# FPGA_MONITOR.net
KiCad netlist of a schematic drawn in Altium Designer
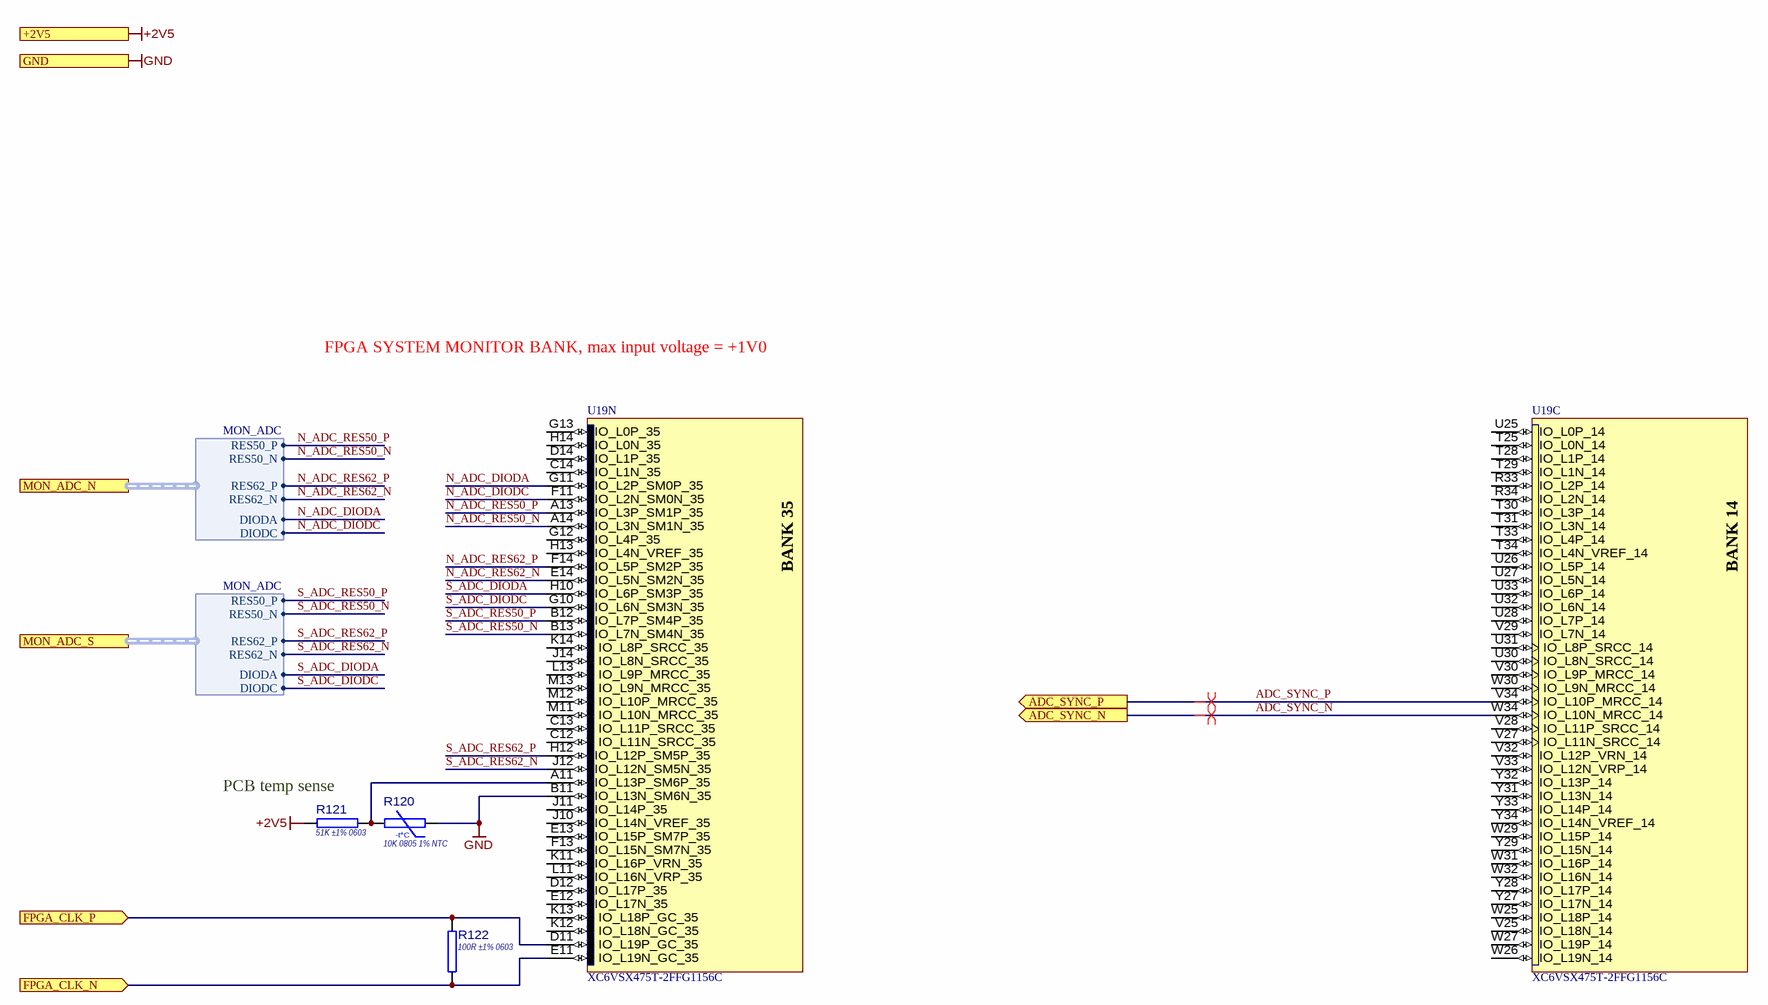
[diagram p0: FPGA_MONITOR.SchDoc]

(export (version "E")
  (design (tool "Eeschema 10.0.6"))
  (components
    (comp (ref "R120")
      (value "10K 0805 1% NTC")
      (footprint "RESC2012N")
      (description "10K NTC resistor 1%  0805 (2012 metric)")
      (fields (field (name "PARTNUMBER") "NTCS0805E3103FLT"))
      (libsource (lib "Omnisys Vault") (part "RES-2PIN-NTC"))
    )
    (comp (ref "R121")
      (value "51K ±1% 0603")
      (footprint "RESC1608N")
      (description "51K ±1% ±100 ppm/˚C 0.10W 75V 0603 (1608 metric)")
      (fields (field (name "POWER") "100mW") (field (name "TOLERANCE") "1%"))
      (libsource (lib "Omnisys Vault") (part "RES-2PIN"))
    )
    (comp (ref "R122")
      (value "100R ±1% 0603")
      (footprint "RESC1608N")
      (description "100R ±1% ±100 ppm/˚C 0.10W 75V 0603 (1608 metric)")
      (fields (field (name "POWER") "100mW") (field (name "TOLERANCE") "1%"))
      (libsource (lib "Omnisys Vault") (part "RES-2PIN"))
    )
    (comp (ref "U19")
      (value "XC6VSX475T-2FFG1156C")
      (footprint "FFG1156")
      (libsource (lib "Altium Content Vault") (part "FPGA-XVR6-XC6VXXXXXT-GA1156"))
    )
  )
  (nets
    (net (code "2") (name "+2V5") (class "Default")
      (node (ref "R121") (pin "1") (pinfunction "1_1") (pintype "passive"))
    )
    (net (code "3") (name "/ADC_SYNC_N") (class "Default")
      (node (ref "U19") (pin "W34") (pinfunction "IO_L10N_MRCC_14_W34") (pintype "bidirectional"))
    )
    (net (code "4") (name "/ADC_SYNC_P") (class "Default")
      (node (ref "U19") (pin "V34") (pinfunction "IO_L10P_MRCC_14_V34") (pintype "bidirectional"))
    )
    (net (code "5") (name "/FPGA_CLK_N") (class "Default")
      (node (ref "R122") (pin "1") (pinfunction "1_1") (pintype "passive"))
      (node (ref "U19") (pin "E11") (pinfunction "IO_L19N_GC_35_E11") (pintype "bidirectional"))
    )
    (net (code "6") (name "/FPGA_CLK_P") (class "Default")
      (node (ref "R122") (pin "2") (pinfunction "2_2") (pintype "passive"))
      (node (ref "U19") (pin "D11") (pinfunction "IO_L19P_GC_35_D11") (pintype "bidirectional"))
    )
    (net (code "7") (name "/N_ADC_DIODA") (class "Default")
      (node (ref "U19") (pin "G11") (pinfunction "IO_L2P_SM0P_35_G11") (pintype "bidirectional"))
    )
    (net (code "8") (name "/N_ADC_DIODC") (class "Default")
      (node (ref "U19") (pin "F11") (pinfunction "IO_L2N_SM0N_35_F11") (pintype "bidirectional"))
    )
    (net (code "9") (name "/N_ADC_RES50_N") (class "Default")
      (node (ref "U19") (pin "A14") (pinfunction "IO_L3N_SM1N_35_A14") (pintype "bidirectional"))
    )
    (net (code "10") (name "/N_ADC_RES50_P") (class "Default")
      (node (ref "U19") (pin "A13") (pinfunction "IO_L3P_SM1P_35_A13") (pintype "bidirectional"))
    )
    (net (code "11") (name "/N_ADC_RES62_N") (class "Default")
      (node (ref "U19") (pin "E14") (pinfunction "IO_L5N_SM2N_35_E14") (pintype "bidirectional"))
    )
    (net (code "12") (name "/N_ADC_RES62_P") (class "Default")
      (node (ref "U19") (pin "F14") (pinfunction "IO_L5P_SM2P_35_F14") (pintype "bidirectional"))
    )
    (net (code "13") (name "/S_ADC_DIODA") (class "Default")
      (node (ref "U19") (pin "H10") (pinfunction "IO_L6P_SM3P_35_H10") (pintype "bidirectional"))
    )
    (net (code "14") (name "/S_ADC_DIODC") (class "Default")
      (node (ref "U19") (pin "G10") (pinfunction "IO_L6N_SM3N_35_G10") (pintype "bidirectional"))
    )
    (net (code "15") (name "/S_ADC_RES50_N") (class "Default")
      (node (ref "U19") (pin "B13") (pinfunction "IO_L7N_SM4N_35_B13") (pintype "bidirectional"))
    )
    (net (code "16") (name "/S_ADC_RES50_P") (class "Default")
      (node (ref "U19") (pin "B12") (pinfunction "IO_L7P_SM4P_35_B12") (pintype "bidirectional"))
    )
    (net (code "17") (name "/S_ADC_RES62_N") (class "Default")
      (node (ref "U19") (pin "J12") (pinfunction "IO_L12N_SM5N_35_J12") (pintype "bidirectional"))
    )
    (net (code "18") (name "/S_ADC_RES62_P") (class "Default")
      (node (ref "U19") (pin "H12") (pinfunction "IO_L12P_SM5P_35_H12") (pintype "bidirectional"))
    )
    (net (code "20") (name "GND") (class "Default")
      (node (ref "R120") (pin "1") (pinfunction "1_1") (pintype "passive"))
      (node (ref "U19") (pin "B11") (pinfunction "IO_L13N_SM6N_35_B11") (pintype "bidirectional"))
    )
    (net (code "21") (name "Net-(U19N-IO_L13P_SM6P_35)") (class "Default")
      (node (ref "R120") (pin "2") (pinfunction "2_2") (pintype "passive"))
      (node (ref "R121") (pin "2") (pinfunction "2_2") (pintype "passive"))
      (node (ref "U19") (pin "A11") (pinfunction "IO_L13P_SM6P_35_A11") (pintype "bidirectional"))
    )
    (net (code "22") (name "unconnected-(U19C-IO_L0N_14-PadT25)") (class "Default")
      (node (ref "U19") (pin "T25") (pinfunction "IO_L0N_14_T25") (pintype "bidirectional"))
    )
    (net (code "23") (name "unconnected-(U19C-IO_L0P_14-PadU25)") (class "Default")
      (node (ref "U19") (pin "U25") (pinfunction "IO_L0P_14_U25") (pintype "bidirectional"))
    )
    (net (code "24") (name "unconnected-(U19C-IO_L1N_14-PadT29)") (class "Default")
      (node (ref "U19") (pin "T29") (pinfunction "IO_L1N_14_T29") (pintype "bidirectional"))
    )
    (net (code "25") (name "unconnected-(U19C-IO_L1P_14-PadT28)") (class "Default")
      (node (ref "U19") (pin "T28") (pinfunction "IO_L1P_14_T28") (pintype "bidirectional"))
    )
    (net (code "26") (name "unconnected-(U19C-IO_L2N_14-PadR34)") (class "Default")
      (node (ref "U19") (pin "R34") (pinfunction "IO_L2N_14_R34") (pintype "bidirectional"))
    )
    (net (code "27") (name "unconnected-(U19C-IO_L2P_14-PadR33)") (class "Default")
      (node (ref "U19") (pin "R33") (pinfunction "IO_L2P_14_R33") (pintype "bidirectional"))
    )
    (net (code "28") (name "unconnected-(U19C-IO_L3N_14-PadT31)") (class "Default")
      (node (ref "U19") (pin "T31") (pinfunction "IO_L3N_14_T31") (pintype "bidirectional"))
    )
    (net (code "29") (name "unconnected-(U19C-IO_L3P_14-PadT30)") (class "Default")
      (node (ref "U19") (pin "T30") (pinfunction "IO_L3P_14_T30") (pintype "bidirectional"))
    )
    (net (code "30") (name "unconnected-(U19C-IO_L4N_VREF_14-PadT34)") (class "Default")
      (node (ref "U19") (pin "T34") (pinfunction "IO_L4N_VREF_14_T34") (pintype "bidirectional"))
    )
    (net (code "31") (name "unconnected-(U19C-IO_L4P_14-PadT33)") (class "Default")
      (node (ref "U19") (pin "T33") (pinfunction "IO_L4P_14_T33") (pintype "bidirectional"))
    )
    (net (code "32") (name "unconnected-(U19C-IO_L5N_14-PadU27)") (class "Default")
      (node (ref "U19") (pin "U27") (pinfunction "IO_L5N_14_U27") (pintype "bidirectional"))
    )
    (net (code "33") (name "unconnected-(U19C-IO_L5P_14-PadU26)") (class "Default")
      (node (ref "U19") (pin "U26") (pinfunction "IO_L5P_14_U26") (pintype "bidirectional"))
    )
    (net (code "34") (name "unconnected-(U19C-IO_L6N_14-PadU32)") (class "Default")
      (node (ref "U19") (pin "U32") (pinfunction "IO_L6N_14_U32") (pintype "bidirectional"))
    )
    (net (code "35") (name "unconnected-(U19C-IO_L6P_14-PadU33)") (class "Default")
      (node (ref "U19") (pin "U33") (pinfunction "IO_L6P_14_U33") (pintype "bidirectional"))
    )
    (net (code "36") (name "unconnected-(U19C-IO_L7N_14-PadV29)") (class "Default")
      (node (ref "U19") (pin "V29") (pinfunction "IO_L7N_14_V29") (pintype "bidirectional"))
    )
    (net (code "37") (name "unconnected-(U19C-IO_L7P_14-PadU28)") (class "Default")
      (node (ref "U19") (pin "U28") (pinfunction "IO_L7P_14_U28") (pintype "bidirectional"))
    )
    (net (code "38") (name "unconnected-(U19C-IO_L8N_SRCC_14-PadU30)") (class "Default")
      (node (ref "U19") (pin "U30") (pinfunction "IO_L8N_SRCC_14_U30") (pintype "bidirectional"))
    )
    (net (code "39") (name "unconnected-(U19C-IO_L8P_SRCC_14-PadU31)") (class "Default")
      (node (ref "U19") (pin "U31") (pinfunction "IO_L8P_SRCC_14_U31") (pintype "bidirectional"))
    )
    (net (code "40") (name "unconnected-(U19C-IO_L9N_MRCC_14-PadW30)") (class "Default")
      (node (ref "U19") (pin "W30") (pinfunction "IO_L9N_MRCC_14_W30") (pintype "bidirectional"))
    )
    (net (code "41") (name "unconnected-(U19C-IO_L9P_MRCC_14-PadV30)") (class "Default")
      (node (ref "U19") (pin "V30") (pinfunction "IO_L9P_MRCC_14_V30") (pintype "bidirectional"))
    )
    (net (code "42") (name "unconnected-(U19C-IO_L11N_SRCC_14-PadV27)") (class "Default")
      (node (ref "U19") (pin "V27") (pinfunction "IO_L11N_SRCC_14_V27") (pintype "bidirectional"))
    )
    (net (code "43") (name "unconnected-(U19C-IO_L11P_SRCC_14-PadV28)") (class "Default")
      (node (ref "U19") (pin "V28") (pinfunction "IO_L11P_SRCC_14_V28") (pintype "bidirectional"))
    )
    (net (code "44") (name "unconnected-(U19C-IO_L12N_VRP_14-PadV33)") (class "Default")
      (node (ref "U19") (pin "V33") (pinfunction "IO_L12N_VRP_14_V33") (pintype "bidirectional"))
    )
    (net (code "45") (name "unconnected-(U19C-IO_L12P_VRN_14-PadV32)") (class "Default")
      (node (ref "U19") (pin "V32") (pinfunction "IO_L12P_VRN_14_V32") (pintype "bidirectional"))
    )
    (net (code "46") (name "unconnected-(U19C-IO_L13N_14-PadY31)") (class "Default")
      (node (ref "U19") (pin "Y31") (pinfunction "IO_L13N_14_Y31") (pintype "bidirectional"))
    )
    (net (code "47") (name "unconnected-(U19C-IO_L13P_14-PadY32)") (class "Default")
      (node (ref "U19") (pin "Y32") (pinfunction "IO_L13P_14_Y32") (pintype "bidirectional"))
    )
    (net (code "48") (name "unconnected-(U19C-IO_L14N_VREF_14-PadY34)") (class "Default")
      (node (ref "U19") (pin "Y34") (pinfunction "IO_L14N_VREF_14_Y34") (pintype "bidirectional"))
    )
    (net (code "49") (name "unconnected-(U19C-IO_L14P_14-PadY33)") (class "Default")
      (node (ref "U19") (pin "Y33") (pinfunction "IO_L14P_14_Y33") (pintype "bidirectional"))
    )
    (net (code "50") (name "unconnected-(U19C-IO_L15N_14-PadY29)") (class "Default")
      (node (ref "U19") (pin "Y29") (pinfunction "IO_L15N_14_Y29") (pintype "bidirectional"))
    )
    (net (code "51") (name "unconnected-(U19C-IO_L15P_14-PadW29)") (class "Default")
      (node (ref "U19") (pin "W29") (pinfunction "IO_L15P_14_W29") (pintype "bidirectional"))
    )
    (net (code "52") (name "unconnected-(U19C-IO_L16N_14-PadW32)") (class "Default")
      (node (ref "U19") (pin "W32") (pinfunction "IO_L16N_14_W32") (pintype "bidirectional"))
    )
    (net (code "53") (name "unconnected-(U19C-IO_L16P_14-PadW31)") (class "Default")
      (node (ref "U19") (pin "W31") (pinfunction "IO_L16P_14_W31") (pintype "bidirectional"))
    )
    (net (code "54") (name "unconnected-(U19C-IO_L17N_14-PadY27)") (class "Default")
      (node (ref "U19") (pin "Y27") (pinfunction "IO_L17N_14_Y27") (pintype "bidirectional"))
    )
    (net (code "55") (name "unconnected-(U19C-IO_L17P_14-PadY28)") (class "Default")
      (node (ref "U19") (pin "Y28") (pinfunction "IO_L17P_14_Y28") (pintype "bidirectional"))
    )
    (net (code "56") (name "unconnected-(U19C-IO_L18N_14-PadV25)") (class "Default")
      (node (ref "U19") (pin "V25") (pinfunction "IO_L18N_14_V25") (pintype "bidirectional"))
    )
    (net (code "57") (name "unconnected-(U19C-IO_L18P_14-PadW25)") (class "Default")
      (node (ref "U19") (pin "W25") (pinfunction "IO_L18P_14_W25") (pintype "bidirectional"))
    )
    (net (code "58") (name "unconnected-(U19C-IO_L19N_14-PadW26)") (class "Default")
      (node (ref "U19") (pin "W26") (pinfunction "IO_L19N_14_W26") (pintype "bidirectional"))
    )
    (net (code "59") (name "unconnected-(U19C-IO_L19P_14-PadW27)") (class "Default")
      (node (ref "U19") (pin "W27") (pinfunction "IO_L19P_14_W27") (pintype "bidirectional"))
    )
    (net (code "60") (name "unconnected-(U19N-IO_L0N_35-PadH14)") (class "Default")
      (node (ref "U19") (pin "H14") (pinfunction "IO_L0N_35_H14") (pintype "bidirectional"))
    )
    (net (code "61") (name "unconnected-(U19N-IO_L0P_35-PadG13)") (class "Default")
      (node (ref "U19") (pin "G13") (pinfunction "IO_L0P_35_G13") (pintype "bidirectional"))
    )
    (net (code "62") (name "unconnected-(U19N-IO_L1N_35-PadC14)") (class "Default")
      (node (ref "U19") (pin "C14") (pinfunction "IO_L1N_35_C14") (pintype "bidirectional"))
    )
    (net (code "63") (name "unconnected-(U19N-IO_L1P_35-PadD14)") (class "Default")
      (node (ref "U19") (pin "D14") (pinfunction "IO_L1P_35_D14") (pintype "bidirectional"))
    )
    (net (code "64") (name "unconnected-(U19N-IO_L4N_VREF_35-PadH13)") (class "Default")
      (node (ref "U19") (pin "H13") (pinfunction "IO_L4N_VREF_35_H13") (pintype "bidirectional"))
    )
    (net (code "65") (name "unconnected-(U19N-IO_L4P_35-PadG12)") (class "Default")
      (node (ref "U19") (pin "G12") (pinfunction "IO_L4P_35_G12") (pintype "bidirectional"))
    )
    (net (code "66") (name "unconnected-(U19N-IO_L8N_SRCC_35-PadJ14)") (class "Default")
      (node (ref "U19") (pin "J14") (pinfunction "IO_L8N_SRCC_35_J14") (pintype "bidirectional"))
    )
    (net (code "67") (name "unconnected-(U19N-IO_L8P_SRCC_35-PadK14)") (class "Default")
      (node (ref "U19") (pin "K14") (pinfunction "IO_L8P_SRCC_35_K14") (pintype "bidirectional"))
    )
    (net (code "68") (name "unconnected-(U19N-IO_L9N_MRCC_35-PadM13)") (class "Default")
      (node (ref "U19") (pin "M13") (pinfunction "IO_L9N_MRCC_35_M13") (pintype "bidirectional"))
    )
    (net (code "69") (name "unconnected-(U19N-IO_L9P_MRCC_35-PadL13)") (class "Default")
      (node (ref "U19") (pin "L13") (pinfunction "IO_L9P_MRCC_35_L13") (pintype "bidirectional"))
    )
    (net (code "70") (name "unconnected-(U19N-IO_L10N_MRCC_35-PadM11)") (class "Default")
      (node (ref "U19") (pin "M11") (pinfunction "IO_L10N_MRCC_35_M11") (pintype "bidirectional"))
    )
    (net (code "71") (name "unconnected-(U19N-IO_L10P_MRCC_35-PadM12)") (class "Default")
      (node (ref "U19") (pin "M12") (pinfunction "IO_L10P_MRCC_35_M12") (pintype "bidirectional"))
    )
    (net (code "72") (name "unconnected-(U19N-IO_L11N_SRCC_35-PadC12)") (class "Default")
      (node (ref "U19") (pin "C12") (pinfunction "IO_L11N_SRCC_35_C12") (pintype "bidirectional"))
    )
    (net (code "73") (name "unconnected-(U19N-IO_L11P_SRCC_35-PadC13)") (class "Default")
      (node (ref "U19") (pin "C13") (pinfunction "IO_L11P_SRCC_35_C13") (pintype "bidirectional"))
    )
    (net (code "74") (name "unconnected-(U19N-IO_L14N_VREF_35-PadJ10)") (class "Default")
      (node (ref "U19") (pin "J10") (pinfunction "IO_L14N_VREF_35_J10") (pintype "bidirectional"))
    )
    (net (code "75") (name "unconnected-(U19N-IO_L14P_35-PadJ11)") (class "Default")
      (node (ref "U19") (pin "J11") (pinfunction "IO_L14P_35_J11") (pintype "bidirectional"))
    )
    (net (code "76") (name "unconnected-(U19N-IO_L15N_SM7N_35-PadF13)") (class "Default")
      (node (ref "U19") (pin "F13") (pinfunction "IO_L15N_SM7N_35_F13") (pintype "bidirectional"))
    )
    (net (code "77") (name "unconnected-(U19N-IO_L15P_SM7P_35-PadE13)") (class "Default")
      (node (ref "U19") (pin "E13") (pinfunction "IO_L15P_SM7P_35_E13") (pintype "bidirectional"))
    )
    (net (code "78") (name "unconnected-(U19N-IO_L16N_VRP_35-PadL11)") (class "Default")
      (node (ref "U19") (pin "L11") (pinfunction "IO_L16N_VRP_35_L11") (pintype "bidirectional"))
    )
    (net (code "79") (name "unconnected-(U19N-IO_L16P_VRN_35-PadK11)") (class "Default")
      (node (ref "U19") (pin "K11") (pinfunction "IO_L16P_VRN_35_K11") (pintype "bidirectional"))
    )
    (net (code "80") (name "unconnected-(U19N-IO_L17N_35-PadE12)") (class "Default")
      (node (ref "U19") (pin "E12") (pinfunction "IO_L17N_35_E12") (pintype "bidirectional"))
    )
    (net (code "81") (name "unconnected-(U19N-IO_L17P_35-PadD12)") (class "Default")
      (node (ref "U19") (pin "D12") (pinfunction "IO_L17P_35_D12") (pintype "bidirectional"))
    )
    (net (code "82") (name "unconnected-(U19N-IO_L18N_GC_35-PadK12)") (class "Default")
      (node (ref "U19") (pin "K12") (pinfunction "IO_L18N_GC_35_K12") (pintype "bidirectional"))
    )
    (net (code "83") (name "unconnected-(U19N-IO_L18P_GC_35-PadK13)") (class "Default")
      (node (ref "U19") (pin "K13") (pinfunction "IO_L18P_GC_35_K13") (pintype "bidirectional"))
    )
  )
)
